# f1_hw_tst.net
KiCad netlist of a schematic drawn in Altium Designer
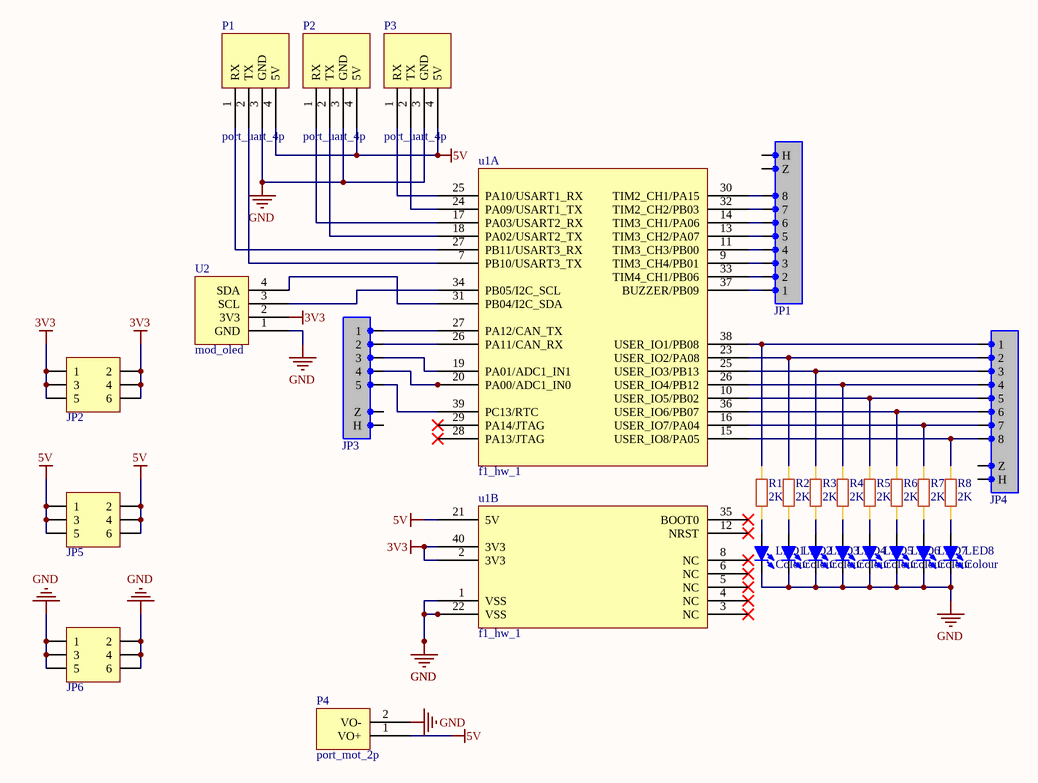
[diagram p0: f1_hw_tst.SchDoc]

(export (version "E")
  (design (tool "Eeschema 10.0.6"))
  (components
    (comp (ref "JP1")
      (value "HDR-1X8")
      (footprint "HDR2.54-LI-8P")
      (description "8P接插件")
      (fields (field (name "版权归属") "源创客"))
      (libsource (lib "14.6-接插件-脚距2.54") (part "Header 8"))
    )
    (comp (ref "JP2")
      (value "Header3X2")
      (footprint "HDR2.54-LI-2x3P")
      (description "3*2P接插件")
      (fields (field (name "版权归属") "源创客"))
      (libsource (lib "14.6-接插件-脚距2.54") (part "Header 3X2"))
    )
    (comp (ref "JP3")
      (value "HDR-1X5")
      (footprint "HDR2.54-LI-5P")
      (description "5P接插件")
      (fields (field (name "版权归属") "源创客"))
      (libsource (lib "14.6-接插件-脚距2.54") (part "Header 5"))
    )
    (comp (ref "JP4")
      (value "HDR-1X8")
      (footprint "HDR2.54-LI-8P")
      (description "8P接插件")
      (fields (field (name "版权归属") "源创客"))
      (libsource (lib "14.6-接插件-脚距2.54") (part "Header 8"))
    )
    (comp (ref "JP5")
      (value "Header3X2")
      (footprint "HDR2.54-LI-2x3P")
      (description "3*2P接插件")
      (fields (field (name "版权归属") "源创客"))
      (libsource (lib "14.6-接插件-脚距2.54") (part "Header 3X2"))
    )
    (comp (ref "JP6")
      (value "Header3X2")
      (footprint "HDR2.54-LI-2x3P")
      (description "3*2P接插件")
      (fields (field (name "版权归属") "源创客"))
      (libsource (lib "14.6-接插件-脚距2.54") (part "Header 3X2"))
    )
    (comp (ref "LED1")
      (value "Colour")
      (footprint "LED 0603R")
      (description "贴片LED")
      (fields (field (name "版权归属") "源创客"))
      (libsource (lib "7.1-LED") (part "LED-SMD"))
    )
    (comp (ref "LED2")
      (value "Colour")
      (footprint "LED 0603R")
      (description "贴片LED")
      (fields (field (name "版权归属") "源创客"))
      (libsource (lib "7.1-LED") (part "LED-SMD"))
    )
    (comp (ref "LED3")
      (value "Colour")
      (footprint "LED 0603R")
      (description "贴片LED")
      (fields (field (name "版权归属") "源创客"))
      (libsource (lib "7.1-LED") (part "LED-SMD"))
    )
    (comp (ref "LED4")
      (value "Colour")
      (footprint "LED 0603R")
      (description "贴片LED")
      (fields (field (name "版权归属") "源创客"))
      (libsource (lib "7.1-LED") (part "LED-SMD"))
    )
    (comp (ref "LED5")
      (value "Colour")
      (footprint "LED 0603R")
      (description "贴片LED")
      (fields (field (name "版权归属") "源创客"))
      (libsource (lib "7.1-LED") (part "LED-SMD"))
    )
    (comp (ref "LED6")
      (value "Colour")
      (footprint "LED 0603R")
      (description "贴片LED")
      (fields (field (name "版权归属") "源创客"))
      (libsource (lib "7.1-LED") (part "LED-SMD"))
    )
    (comp (ref "LED7")
      (value "Colour")
      (footprint "LED 0603R")
      (description "贴片LED")
      (fields (field (name "版权归属") "源创客"))
      (libsource (lib "7.1-LED") (part "LED-SMD"))
    )
    (comp (ref "LED8")
      (value "Colour")
      (footprint "LED 0603R")
      (description "贴片LED")
      (fields (field (name "版权归属") "源创客"))
      (libsource (lib "7.1-LED") (part "LED-SMD"))
    )
    (comp (ref "P1")
      (value "port_uart_4p")
      (footprint "XH2.54_4P")
      (description "串口接口/SPP蓝牙模块\r\nXH2.54弯排针4p/4p排母")
      (libsource (lib "userLib") (part "port_uart_4p"))
    )
    (comp (ref "P2")
      (value "port_uart_4p")
      (footprint "XH2.54_4P")
      (description "串口接口/SPP蓝牙模块\r\nXH2.54弯排针4p/4p排母")
      (libsource (lib "userLib") (part "port_uart_4p"))
    )
    (comp (ref "P3")
      (value "port_uart_4p")
      (footprint "XH2.54_4P")
      (description "串口接口/SPP蓝牙模块\r\nXH2.54弯排针4p/4p排母")
      (libsource (lib "userLib") (part "port_uart_4p"))
    )
    (comp (ref "P4")
      (value "port_mot_2p")
      (footprint "XH2.54_2P")
      (description "开环直流电机接口\r\nXH2.54弯排针2p")
      (libsource (lib "userLib") (part "port_mot_2p"))
    )
    (comp (ref "R1")
      (value "2K")
      (footprint "R 0603_L")
      (description "贴片电阻1%精度")
      (libsource (lib "Propitious Clouds_SCHLIB") (part "电阻"))
    )
    (comp (ref "R2")
      (value "2K")
      (footprint "R 0603_L")
      (description "贴片电阻1%精度")
      (libsource (lib "Propitious Clouds_SCHLIB") (part "电阻"))
    )
    (comp (ref "R3")
      (value "2K")
      (footprint "R 0603_L")
      (description "贴片电阻1%精度")
      (libsource (lib "Propitious Clouds_SCHLIB") (part "电阻"))
    )
    (comp (ref "R4")
      (value "2K")
      (footprint "R 0603_L")
      (description "贴片电阻1%精度")
      (libsource (lib "Propitious Clouds_SCHLIB") (part "电阻"))
    )
    (comp (ref "R5")
      (value "2K")
      (footprint "R 0603_L")
      (description "贴片电阻1%精度")
      (libsource (lib "Propitious Clouds_SCHLIB") (part "电阻"))
    )
    (comp (ref "R6")
      (value "2K")
      (footprint "R 0603_L")
      (description "贴片电阻1%精度")
      (libsource (lib "Propitious Clouds_SCHLIB") (part "电阻"))
    )
    (comp (ref "R7")
      (value "2K")
      (footprint "R 0603_L")
      (description "贴片电阻1%精度")
      (libsource (lib "Propitious Clouds_SCHLIB") (part "电阻"))
    )
    (comp (ref "R8")
      (value "2K")
      (footprint "R 0603_L")
      (description "贴片电阻1%精度")
      (libsource (lib "Propitious Clouds_SCHLIB") (part "电阻"))
    )
    (comp (ref "u1")
      (value "f1_hw_1")
      (footprint "f1_hw_1")
      (description "F103C8T6最小系统_1")
      (libsource (lib "userLib") (part "f1_hw_1"))
    )
    (comp (ref "U2")
      (value "mod_oled")
      (footprint "mod_oled")
      (description "oled模块\r\n4p排母")
      (libsource (lib "userLib") (part "mod_oled"))
    )
  )
  (nets
    (net (code "1") (name "3V3") (class "Default")
      (node (ref "JP2") (pin "1") (pinfunction "1_1") (pintype "passive"))
      (node (ref "JP2") (pin "2") (pinfunction "2_2") (pintype "passive"))
      (node (ref "JP2") (pin "3") (pinfunction "3_3") (pintype "passive"))
      (node (ref "JP2") (pin "4") (pinfunction "4_4") (pintype "passive"))
      (node (ref "JP2") (pin "5") (pinfunction "5_5") (pintype "passive"))
      (node (ref "JP2") (pin "6") (pinfunction "6_6") (pintype "passive"))
      (node (ref "U2") (pin "2") (pinfunction "3V3_2") (pintype "passive"))
      (node (ref "u1") (pin "2") (pinfunction "3V3_2") (pintype "passive"))
      (node (ref "u1") (pin "40") (pinfunction "3V3_40") (pintype "passive"))
    )
    (net (code "2") (name "5V") (class "Default")
      (node (ref "JP5") (pin "1") (pinfunction "1_1") (pintype "passive"))
      (node (ref "JP5") (pin "2") (pinfunction "2_2") (pintype "passive"))
      (node (ref "JP5") (pin "3") (pinfunction "3_3") (pintype "passive"))
      (node (ref "JP5") (pin "4") (pinfunction "4_4") (pintype "passive"))
      (node (ref "JP5") (pin "5") (pinfunction "5_5") (pintype "passive"))
      (node (ref "JP5") (pin "6") (pinfunction "6_6") (pintype "passive"))
      (node (ref "P1") (pin "4") (pinfunction "5V_4") (pintype "passive"))
      (node (ref "P2") (pin "4") (pinfunction "5V_4") (pintype "passive"))
      (node (ref "P3") (pin "4") (pinfunction "5V_4") (pintype "passive"))
      (node (ref "P4") (pin "1") (pinfunction "VO+_1") (pintype "passive"))
      (node (ref "u1") (pin "21") (pinfunction "5V_21") (pintype "passive"))
    )
    (net (code "3") (name "GND") (class "Default")
      (node (ref "JP6") (pin "1") (pinfunction "1_1") (pintype "passive"))
      (node (ref "JP6") (pin "2") (pinfunction "2_2") (pintype "passive"))
      (node (ref "JP6") (pin "3") (pinfunction "3_3") (pintype "passive"))
      (node (ref "JP6") (pin "4") (pinfunction "4_4") (pintype "passive"))
      (node (ref "JP6") (pin "5") (pinfunction "5_5") (pintype "passive"))
      (node (ref "JP6") (pin "6") (pinfunction "6_6") (pintype "passive"))
      (node (ref "LED1") (pin "2") (pinfunction "K_2") (pintype "passive"))
      (node (ref "LED2") (pin "2") (pinfunction "K_2") (pintype "passive"))
      (node (ref "LED3") (pin "2") (pinfunction "K_2") (pintype "passive"))
      (node (ref "LED4") (pin "2") (pinfunction "K_2") (pintype "passive"))
      (node (ref "LED5") (pin "2") (pinfunction "K_2") (pintype "passive"))
      (node (ref "LED6") (pin "2") (pinfunction "K_2") (pintype "passive"))
      (node (ref "LED7") (pin "2") (pinfunction "K_2") (pintype "passive"))
      (node (ref "LED8") (pin "2") (pinfunction "K_2") (pintype "passive"))
      (node (ref "P1") (pin "3") (pinfunction "GND_3") (pintype "passive"))
      (node (ref "P2") (pin "3") (pinfunction "GND_3") (pintype "passive"))
      (node (ref "P3") (pin "3") (pinfunction "GND_3") (pintype "passive"))
      (node (ref "P4") (pin "2") (pinfunction "VO-_2") (pintype "passive"))
      (node (ref "U2") (pin "1") (pinfunction "GND_1") (pintype "passive"))
      (node (ref "u1") (pin "1") (pinfunction "VSS_1") (pintype "passive"))
      (node (ref "u1") (pin "22") (pinfunction "VSS_22") (pintype "passive"))
    )
    (net (code "4") (name "Net-(LED1-A)") (class "Default")
      (node (ref "LED1") (pin "1") (pinfunction "A_1") (pintype "passive"))
      (node (ref "R1") (pin "2") (pinfunction "2_2") (pintype "passive"))
    )
    (net (code "5") (name "Net-(LED2-A)") (class "Default")
      (node (ref "LED2") (pin "1") (pinfunction "A_1") (pintype "passive"))
      (node (ref "R2") (pin "2") (pinfunction "2_2") (pintype "passive"))
    )
    (net (code "6") (name "Net-(LED3-A)") (class "Default")
      (node (ref "LED3") (pin "1") (pinfunction "A_1") (pintype "passive"))
      (node (ref "R3") (pin "2") (pinfunction "2_2") (pintype "passive"))
    )
    (net (code "7") (name "Net-(LED4-A)") (class "Default")
      (node (ref "LED4") (pin "1") (pinfunction "A_1") (pintype "passive"))
      (node (ref "R4") (pin "2") (pinfunction "2_2") (pintype "passive"))
    )
    (net (code "8") (name "Net-(LED5-A)") (class "Default")
      (node (ref "LED5") (pin "1") (pinfunction "A_1") (pintype "passive"))
      (node (ref "R5") (pin "2") (pinfunction "2_2") (pintype "passive"))
    )
    (net (code "9") (name "Net-(LED6-A)") (class "Default")
      (node (ref "LED6") (pin "1") (pinfunction "A_1") (pintype "passive"))
      (node (ref "R6") (pin "2") (pinfunction "2_2") (pintype "passive"))
    )
    (net (code "10") (name "Net-(LED7-A)") (class "Default")
      (node (ref "LED7") (pin "1") (pinfunction "A_1") (pintype "passive"))
      (node (ref "R7") (pin "2") (pinfunction "2_2") (pintype "passive"))
    )
    (net (code "11") (name "Net-(LED8-A)") (class "Default")
      (node (ref "LED8") (pin "1") (pinfunction "A_1") (pintype "passive"))
      (node (ref "R8") (pin "2") (pinfunction "2_2") (pintype "passive"))
    )
    (net (code "12") (name "Net-(P1-RX)") (class "Default")
      (node (ref "P1") (pin "1") (pinfunction "RX_1") (pintype "passive"))
      (node (ref "u1") (pin "27") (pinfunction "PB11/USART3_RX_27") (pintype "passive"))
    )
    (net (code "13") (name "Net-(P1-TX)") (class "Default")
      (node (ref "P1") (pin "2") (pinfunction "TX_2") (pintype "passive"))
      (node (ref "u1") (pin "7") (pinfunction "PB10/USART3_TX_7") (pintype "passive"))
    )
    (net (code "14") (name "Net-(P2-RX)") (class "Default")
      (node (ref "P2") (pin "1") (pinfunction "RX_1") (pintype "passive"))
      (node (ref "u1") (pin "17") (pinfunction "PA03/USART2_RX_17") (pintype "passive"))
    )
    (net (code "15") (name "Net-(P2-TX)") (class "Default")
      (node (ref "P2") (pin "2") (pinfunction "TX_2") (pintype "passive"))
      (node (ref "u1") (pin "18") (pinfunction "PA02/USART2_TX_18") (pintype "passive"))
    )
    (net (code "16") (name "Net-(P3-RX)") (class "Default")
      (node (ref "P3") (pin "1") (pinfunction "RX_1") (pintype "passive"))
      (node (ref "u1") (pin "25") (pinfunction "PA10/USART1_RX_25") (pintype "passive"))
    )
    (net (code "17") (name "Net-(P3-TX)") (class "Default")
      (node (ref "P3") (pin "2") (pinfunction "TX_2") (pintype "passive"))
      (node (ref "u1") (pin "24") (pinfunction "PA09/USART1_TX_24") (pintype "passive"))
    )
    (net (code "18") (name "Net-(U2-SCL)") (class "Default")
      (node (ref "U2") (pin "3") (pinfunction "SCL_3") (pintype "passive"))
      (node (ref "u1") (pin "34") (pinfunction "PB05/I2C_SCL_34") (pintype "passive"))
    )
    (net (code "19") (name "Net-(U2-SDA)") (class "Default")
      (node (ref "U2") (pin "4") (pinfunction "SDA_4") (pintype "passive"))
      (node (ref "u1") (pin "31") (pinfunction "PB04/I2C_SDA_31") (pintype "passive"))
    )
    (net (code "20") (name "Net-(u1A-BUZZER{slash}PB09)") (class "Default")
      (node (ref "JP1") (pin "1") (pinfunction "1_1") (pintype "passive"))
      (node (ref "u1") (pin "37") (pinfunction "BUZZER/PB09_37") (pintype "passive"))
    )
    (net (code "21") (name "Net-(u1A-PA00{slash}ADC1_IN0)") (class "Default")
      (node (ref "JP3") (pin "4") (pinfunction "4_4") (pintype "passive"))
      (node (ref "u1") (pin "20") (pinfunction "PA00/ADC1_IN0_20") (pintype "passive"))
    )
    (net (code "22") (name "Net-(u1A-PA01{slash}ADC1_IN1)") (class "Default")
      (node (ref "JP3") (pin "3") (pinfunction "3_3") (pintype "passive"))
      (node (ref "u1") (pin "19") (pinfunction "PA01/ADC1_IN1_19") (pintype "passive"))
    )
    (net (code "23") (name "Net-(u1A-PA11{slash}CAN_RX)") (class "Default")
      (node (ref "JP3") (pin "2") (pinfunction "2_2") (pintype "passive"))
      (node (ref "u1") (pin "26") (pinfunction "PA11/CAN_RX_26") (pintype "passive"))
    )
    (net (code "24") (name "Net-(u1A-PA12{slash}CAN_TX)") (class "Default")
      (node (ref "JP3") (pin "1") (pinfunction "1_1") (pintype "passive"))
      (node (ref "u1") (pin "27") (pinfunction "PA12/CAN_TX_27") (pintype "passive"))
    )
    (net (code "25") (name "Net-(u1A-PC13{slash}RTC)") (class "Default")
      (node (ref "JP3") (pin "5") (pinfunction "5_5") (pintype "passive"))
      (node (ref "u1") (pin "39") (pinfunction "PC13/RTC_39") (pintype "passive"))
    )
    (net (code "26") (name "Net-(u1A-TIM2_CH1{slash}PA15)") (class "Default")
      (node (ref "JP1") (pin "8") (pinfunction "8_8") (pintype "passive"))
      (node (ref "u1") (pin "30") (pinfunction "TIM2_CH1/PA15_30") (pintype "passive"))
    )
    (net (code "27") (name "Net-(u1A-TIM2_CH2{slash}PB03)") (class "Default")
      (node (ref "JP1") (pin "7") (pinfunction "7_7") (pintype "passive"))
      (node (ref "u1") (pin "32") (pinfunction "TIM2_CH2/PB03_32") (pintype "passive"))
    )
    (net (code "28") (name "Net-(u1A-TIM3_CH1{slash}PA06)") (class "Default")
      (node (ref "JP1") (pin "6") (pinfunction "6_6") (pintype "passive"))
      (node (ref "u1") (pin "14") (pinfunction "TIM3_CH1/PA06_14") (pintype "passive"))
    )
    (net (code "29") (name "Net-(u1A-TIM3_CH2{slash}PA07)") (class "Default")
      (node (ref "JP1") (pin "5") (pinfunction "5_5") (pintype "passive"))
      (node (ref "u1") (pin "13") (pinfunction "TIM3_CH2/PA07_13") (pintype "passive"))
    )
    (net (code "30") (name "Net-(u1A-TIM3_CH3{slash}PB00)") (class "Default")
      (node (ref "JP1") (pin "4") (pinfunction "4_4") (pintype "passive"))
      (node (ref "u1") (pin "11") (pinfunction "TIM3_CH3/PB00_11") (pintype "passive"))
    )
    (net (code "31") (name "Net-(u1A-TIM3_CH4{slash}PB01)") (class "Default")
      (node (ref "JP1") (pin "3") (pinfunction "3_3") (pintype "passive"))
      (node (ref "u1") (pin "9") (pinfunction "TIM3_CH4/PB01_9") (pintype "passive"))
    )
    (net (code "32") (name "Net-(u1A-TIM4_CH1{slash}PB06)") (class "Default")
      (node (ref "JP1") (pin "2") (pinfunction "2_2") (pintype "passive"))
      (node (ref "u1") (pin "33") (pinfunction "TIM4_CH1/PB06_33") (pintype "passive"))
    )
    (net (code "33") (name "Net-(u1A-USER_IO1{slash}PB08)") (class "Default")
      (node (ref "JP4") (pin "1") (pinfunction "1_1") (pintype "passive"))
      (node (ref "R1") (pin "1") (pinfunction "1_1") (pintype "passive"))
      (node (ref "u1") (pin "38") (pinfunction "USER_IO1/PB08_38") (pintype "passive"))
    )
    (net (code "34") (name "Net-(u1A-USER_IO2{slash}PA08)") (class "Default")
      (node (ref "JP4") (pin "2") (pinfunction "2_2") (pintype "passive"))
      (node (ref "R2") (pin "1") (pinfunction "1_1") (pintype "passive"))
      (node (ref "u1") (pin "23") (pinfunction "USER_IO2/PA08_23") (pintype "passive"))
    )
    (net (code "35") (name "Net-(u1A-USER_IO3{slash}PB13)") (class "Default")
      (node (ref "JP4") (pin "3") (pinfunction "3_3") (pintype "passive"))
      (node (ref "R3") (pin "1") (pinfunction "1_1") (pintype "passive"))
      (node (ref "u1") (pin "25") (pinfunction "USER_IO3/PB13_25") (pintype "passive"))
    )
    (net (code "36") (name "Net-(u1A-USER_IO4{slash}PB12)") (class "Default")
      (node (ref "JP4") (pin "4") (pinfunction "4_4") (pintype "passive"))
      (node (ref "R4") (pin "1") (pinfunction "1_1") (pintype "passive"))
      (node (ref "u1") (pin "26") (pinfunction "USER_IO4/PB12_26") (pintype "passive"))
    )
    (net (code "37") (name "Net-(u1A-USER_IO5{slash}PB02)") (class "Default")
      (node (ref "JP4") (pin "5") (pinfunction "5_5") (pintype "passive"))
      (node (ref "R5") (pin "1") (pinfunction "1_1") (pintype "passive"))
      (node (ref "u1") (pin "10") (pinfunction "USER_IO5/PB02_10") (pintype "passive"))
    )
    (net (code "38") (name "Net-(u1A-USER_IO6{slash}PB07)") (class "Default")
      (node (ref "JP4") (pin "6") (pinfunction "6_6") (pintype "passive"))
      (node (ref "R6") (pin "1") (pinfunction "1_1") (pintype "passive"))
      (node (ref "u1") (pin "36") (pinfunction "USER_IO6/PB07_36") (pintype "passive"))
    )
    (net (code "39") (name "Net-(u1A-USER_IO7{slash}PA04)") (class "Default")
      (node (ref "JP4") (pin "7") (pinfunction "7_7") (pintype "passive"))
      (node (ref "R7") (pin "1") (pinfunction "1_1") (pintype "passive"))
      (node (ref "u1") (pin "16") (pinfunction "USER_IO7/PA04_16") (pintype "passive"))
    )
    (net (code "40") (name "Net-(u1A-USER_IO8{slash}PA05)") (class "Default")
      (node (ref "JP4") (pin "8") (pinfunction "8_8") (pintype "passive"))
      (node (ref "R8") (pin "1") (pinfunction "1_1") (pintype "passive"))
      (node (ref "u1") (pin "15") (pinfunction "USER_IO8/PA05_15") (pintype "passive"))
    )
    (net (code "41") (name "unconnected-(JP1-H-Pad100)") (class "Default")
      (node (ref "JP1") (pin "100") (pinfunction "H_100") (pintype "passive"))
    )
    (net (code "42") (name "unconnected-(JP1-Z-Pad0)") (class "Default")
      (node (ref "JP1") (pin "0") (pinfunction "Z_0") (pintype "passive"))
    )
    (net (code "43") (name "unconnected-(JP3-H-Pad100)") (class "Default")
      (node (ref "JP3") (pin "100") (pinfunction "H_100") (pintype "passive"))
    )
    (net (code "44") (name "unconnected-(JP3-Z-Pad0)") (class "Default")
      (node (ref "JP3") (pin "0") (pinfunction "Z_0") (pintype "passive"))
    )
    (net (code "45") (name "unconnected-(JP4-H-Pad100)") (class "Default")
      (node (ref "JP4") (pin "100") (pinfunction "H_100") (pintype "passive"))
    )
    (net (code "46") (name "unconnected-(JP4-Z-Pad0)") (class "Default")
      (node (ref "JP4") (pin "0") (pinfunction "Z_0") (pintype "passive"))
    )
    (net (code "47") (name "unconnected-(u1A-PA13{slash}JTAG-Pad28)") (class "Default")
      (node (ref "u1") (pin "28") (pinfunction "PA13/JTAG_28") (pintype "passive+no_connect"))
    )
    (net (code "48") (name "unconnected-(u1A-PA14{slash}JTAG-Pad29)") (class "Default")
      (node (ref "u1") (pin "29") (pinfunction "PA14/JTAG_29") (pintype "passive+no_connect"))
    )
    (net (code "49") (name "unconnected-(u1B-BOOT0-Pad35)") (class "Default")
      (node (ref "u1") (pin "35") (pinfunction "BOOT0_35") (pintype "passive+no_connect"))
    )
    (net (code "50") (name "unconnected-(u1B-NC-Pad3)") (class "Default")
      (node (ref "u1") (pin "3") (pinfunction "NC_3") (pintype "passive+no_connect"))
    )
    (net (code "51") (name "unconnected-(u1B-NC-Pad4)") (class "Default")
      (node (ref "u1") (pin "4") (pinfunction "NC_4") (pintype "passive+no_connect"))
    )
    (net (code "52") (name "unconnected-(u1B-NC-Pad5)") (class "Default")
      (node (ref "u1") (pin "5") (pinfunction "NC_5") (pintype "passive+no_connect"))
    )
    (net (code "53") (name "unconnected-(u1B-NC-Pad6)") (class "Default")
      (node (ref "u1") (pin "6") (pinfunction "NC_6") (pintype "passive+no_connect"))
    )
    (net (code "54") (name "unconnected-(u1B-NC-Pad8)") (class "Default")
      (node (ref "u1") (pin "8") (pinfunction "NC_8") (pintype "passive+no_connect"))
    )
    (net (code "55") (name "unconnected-(u1B-NRST-Pad12)") (class "Default")
      (node (ref "u1") (pin "12") (pinfunction "NRST_12") (pintype "passive+no_connect"))
    )
  )
)
